# LM298.net
KiCad netlist of a schematic drawn in Altium Designer
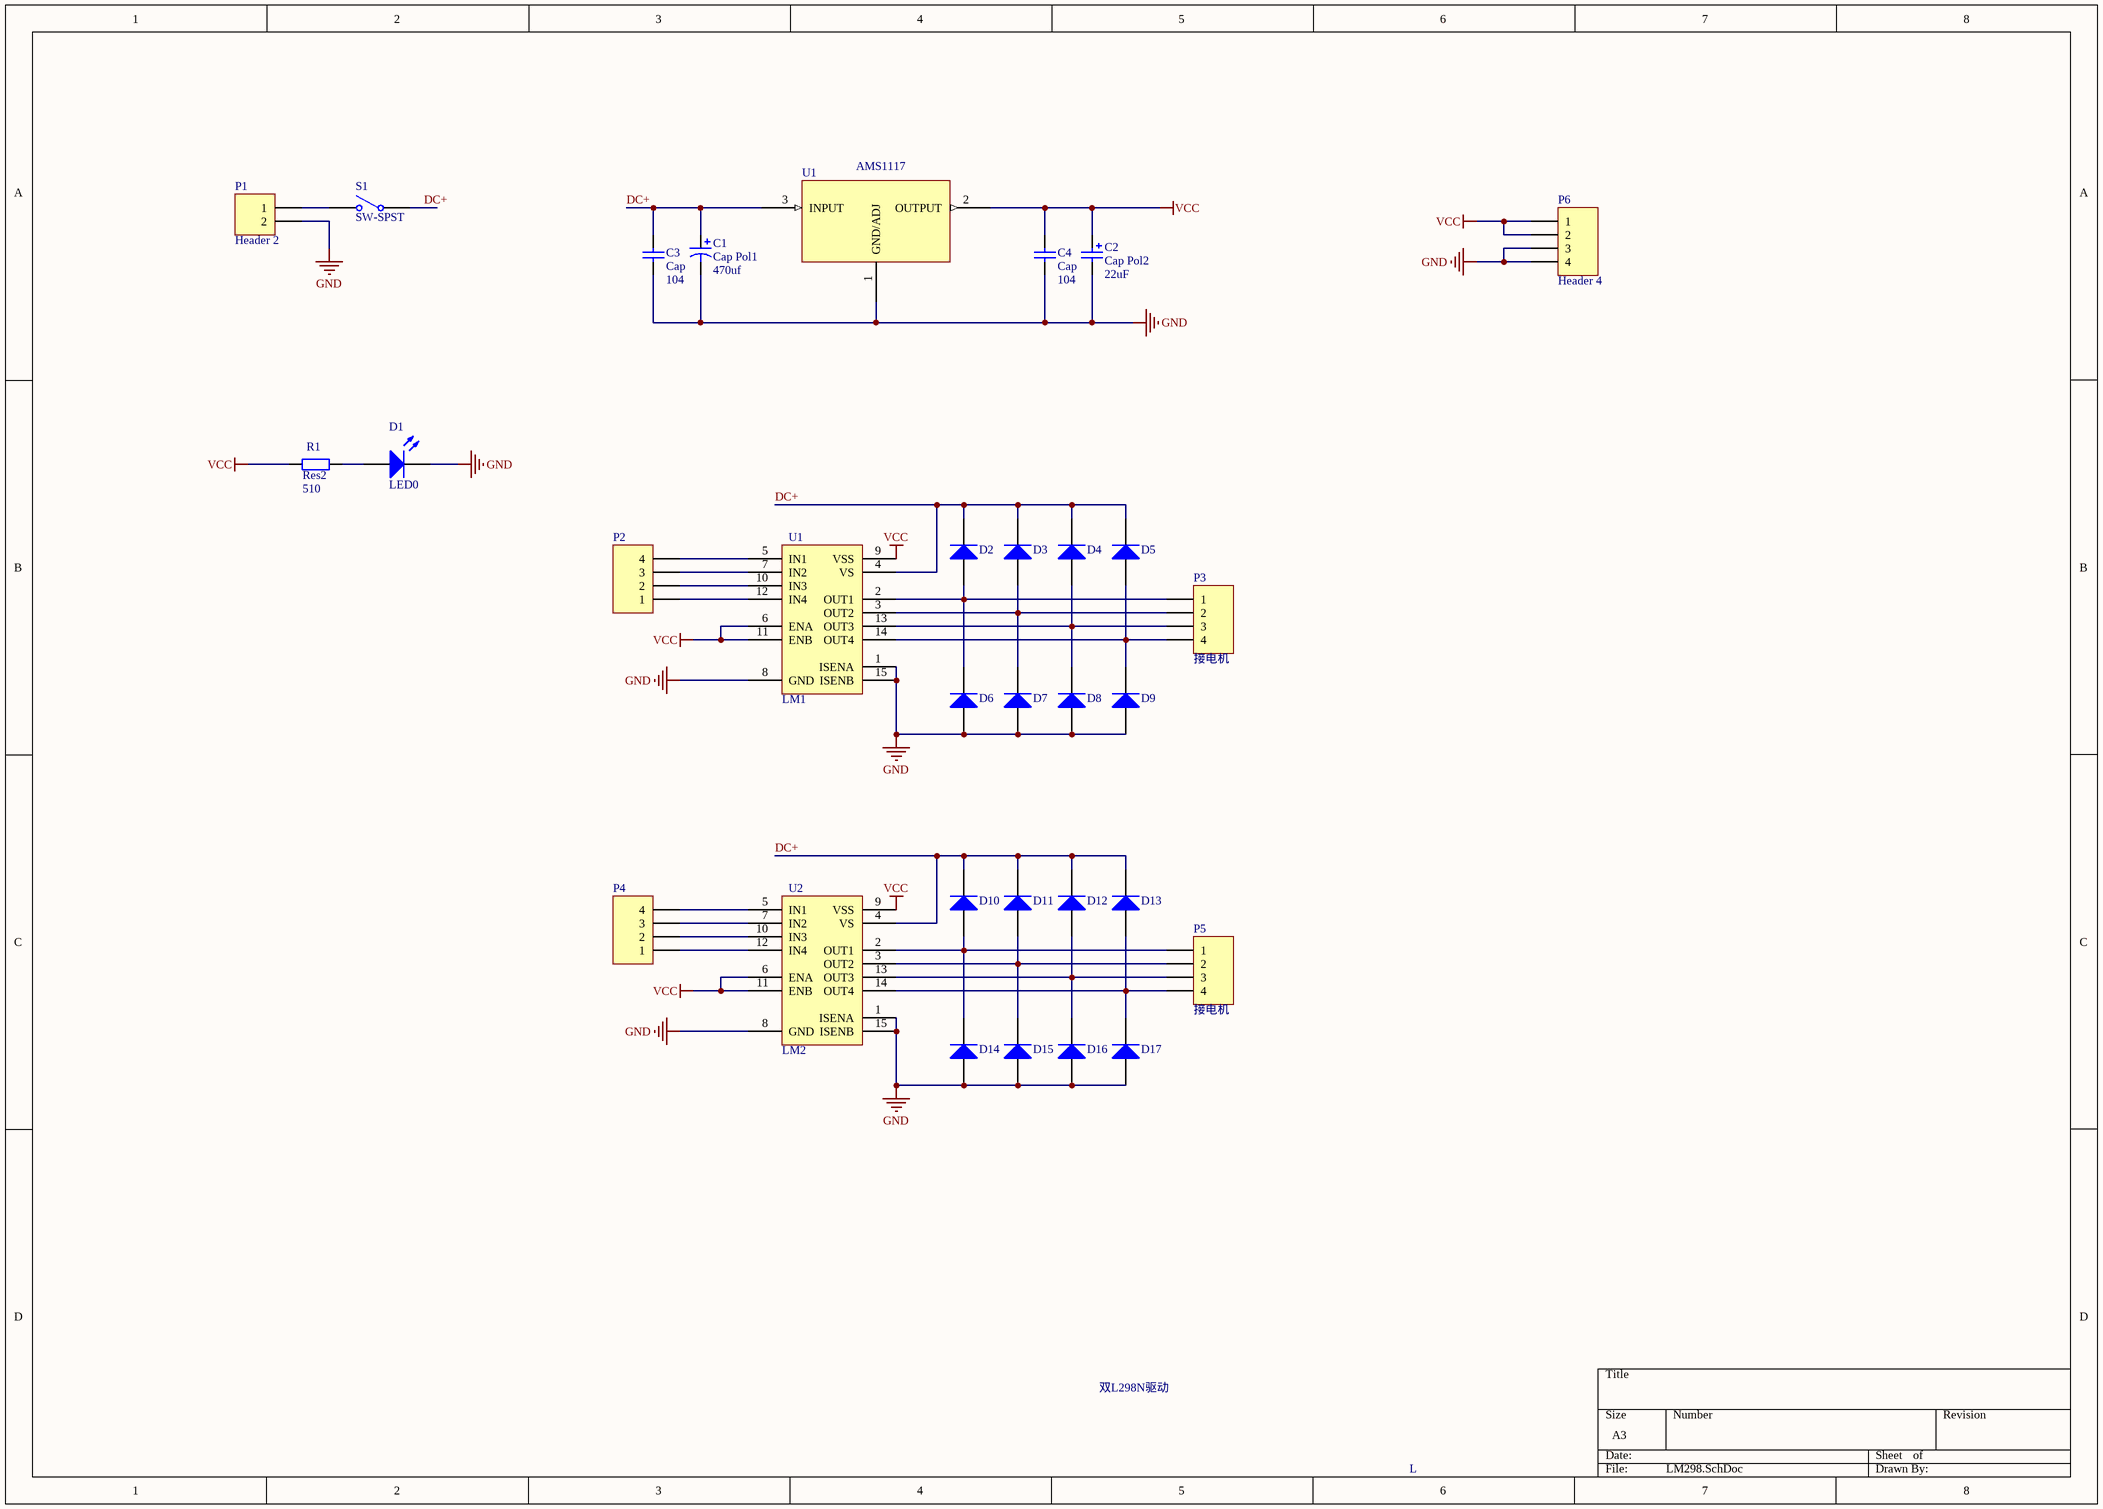
[diagram p0: LM298.SchDoc]

(export (version "E")
  (design (tool "Eeschema 10.0.6"))
  (components
    (comp (ref "C1")
      (value "Cap Pol1")
      (footprint "CAP-E1")
      (description "Polarized Capacitor (Radial)")
      (fields (field (name "ALTIUM_VALUE") "470uf") (field (name "PUBLISHER") "Altium Limited"))
      (libsource (lib "Miscellaneous Devices") (part "Cap Pol1"))
    )
    (comp (ref "C2")
      (value "Cap Pol2")
      (footprint "C-RB-8")
      (description "Polarized Capacitor (Axial)")
      (fields (field (name "ALTIUM_VALUE") "22uF") (field (name "PUBLISHER") "Altium Limited"))
      (libsource (lib "Miscellaneous Devices") (part "Cap Pol2"))
    )
    (comp (ref "C3")
      (value "Cap")
      (footprint "C-0805")
      (description "Capacitor")
      (fields (field (name "ALTIUM_VALUE") "104") (field (name "PUBLISHER") "Altium Limited"))
      (libsource (lib "Miscellaneous Devices") (part "Cap"))
    )
    (comp (ref "C4")
      (value "Cap")
      (footprint "C-0805")
      (description "Capacitor")
      (fields (field (name "ALTIUM_VALUE") "104") (field (name "PUBLISHER") "Altium Limited"))
      (libsource (lib "Miscellaneous Devices") (part "Cap"))
    )
    (comp (ref "D1")
      (value "LED0")
      (footprint "LED")
      (description "Typical INFRARED GaAs LED")
      (fields (field (name "PUBLISHER") "Altium Limited"))
      (libsource (lib "Miscellaneous Devices") (part "LED0"))
    )
    (comp (ref "D2")
      (value "Diode 1N4007")
      (footprint "DIODE-AXL")
      (description "1 Amp General Purpose Rectifier")
      (fields (field (name "PUBLISHER") "Altium Limited"))
      (libsource (lib "Miscellaneous Devices") (part "Diode 1N4007"))
    )
    (comp (ref "D3")
      (value "Diode 1N4007")
      (footprint "DIODE-AXL")
      (description "1 Amp General Purpose Rectifier")
      (fields (field (name "PUBLISHER") "Altium Limited"))
      (libsource (lib "Miscellaneous Devices") (part "Diode 1N4007"))
    )
    (comp (ref "D4")
      (value "Diode 1N4007")
      (footprint "DIODE-AXL")
      (description "1 Amp General Purpose Rectifier")
      (fields (field (name "PUBLISHER") "Altium Limited"))
      (libsource (lib "Miscellaneous Devices") (part "Diode 1N4007"))
    )
    (comp (ref "D5")
      (value "Diode 1N4007")
      (footprint "DIODE-AXL")
      (description "1 Amp General Purpose Rectifier")
      (fields (field (name "PUBLISHER") "Altium Limited"))
      (libsource (lib "Miscellaneous Devices") (part "Diode 1N4007"))
    )
    (comp (ref "D6")
      (value "Diode 1N4007")
      (footprint "DIODE-AXL")
      (description "1 Amp General Purpose Rectifier")
      (fields (field (name "PUBLISHER") "Altium Limited"))
      (libsource (lib "Miscellaneous Devices") (part "Diode 1N4007"))
    )
    (comp (ref "D7")
      (value "Diode 1N4007")
      (footprint "DIODE-AXL")
      (description "1 Amp General Purpose Rectifier")
      (fields (field (name "PUBLISHER") "Altium Limited"))
      (libsource (lib "Miscellaneous Devices") (part "Diode 1N4007"))
    )
    (comp (ref "D8")
      (value "Diode 1N4007")
      (footprint "DIODE-AXL")
      (description "1 Amp General Purpose Rectifier")
      (fields (field (name "PUBLISHER") "Altium Limited"))
      (libsource (lib "Miscellaneous Devices") (part "Diode 1N4007"))
    )
    (comp (ref "D9")
      (value "Diode 1N4007")
      (footprint "DIODE-AXL")
      (description "1 Amp General Purpose Rectifier")
      (fields (field (name "PUBLISHER") "Altium Limited"))
      (libsource (lib "Miscellaneous Devices") (part "Diode 1N4007"))
    )
    (comp (ref "D10")
      (value "Diode 1N4007")
      (footprint "DIODE-AXL")
      (description "1 Amp General Purpose Rectifier")
      (fields (field (name "PUBLISHER") "Altium Limited"))
      (libsource (lib "Miscellaneous Devices") (part "Diode 1N4007"))
    )
    (comp (ref "D11")
      (value "Diode 1N4007")
      (footprint "DIODE-AXL")
      (description "1 Amp General Purpose Rectifier")
      (fields (field (name "PUBLISHER") "Altium Limited"))
      (libsource (lib "Miscellaneous Devices") (part "Diode 1N4007"))
    )
    (comp (ref "D12")
      (value "Diode 1N4007")
      (footprint "DIODE-AXL")
      (description "1 Amp General Purpose Rectifier")
      (fields (field (name "PUBLISHER") "Altium Limited"))
      (libsource (lib "Miscellaneous Devices") (part "Diode 1N4007"))
    )
    (comp (ref "D13")
      (value "Diode 1N4007")
      (footprint "DIODE-AXL")
      (description "1 Amp General Purpose Rectifier")
      (fields (field (name "PUBLISHER") "Altium Limited"))
      (libsource (lib "Miscellaneous Devices") (part "Diode 1N4007"))
    )
    (comp (ref "D14")
      (value "Diode 1N4007")
      (footprint "DIODE-AXL")
      (description "1 Amp General Purpose Rectifier")
      (fields (field (name "PUBLISHER") "Altium Limited"))
      (libsource (lib "Miscellaneous Devices") (part "Diode 1N4007"))
    )
    (comp (ref "D15")
      (value "Diode 1N4007")
      (footprint "DIODE-AXL")
      (description "1 Amp General Purpose Rectifier")
      (fields (field (name "PUBLISHER") "Altium Limited"))
      (libsource (lib "Miscellaneous Devices") (part "Diode 1N4007"))
    )
    (comp (ref "D16")
      (value "Diode 1N4007")
      (footprint "DIODE-AXL")
      (description "1 Amp General Purpose Rectifier")
      (fields (field (name "PUBLISHER") "Altium Limited"))
      (libsource (lib "Miscellaneous Devices") (part "Diode 1N4007"))
    )
    (comp (ref "D17")
      (value "Diode 1N4007")
      (footprint "DIODE-AXL")
      (description "1 Amp General Purpose Rectifier")
      (fields (field (name "PUBLISHER") "Altium Limited"))
      (libsource (lib "Miscellaneous Devices") (part "Diode 1N4007"))
    )
    (comp (ref "LM1") (value "U1") (footprint "L298N") (libsource (lib "常用1") (part "LM298N")))
    (comp (ref "LM2") (value "U2") (footprint "L298N") (libsource (lib "常用1") (part "LM298N")))
    (comp (ref "P1")
      (value "Header 2")
      (footprint "接线柱")
      (description "Header, 2-Pin")
      (fields (field (name "PUBLISHER") "Altium Limited"))
      (libsource (lib "Miscellaneous Connectors") (part "Header 2"))
    )
    (comp (ref "P2")
      (value "~")
      (footprint "HDR1X4")
      (description "Header, 4-Pin")
      (fields (field (name "PUBLISHER") "Altium Limited"))
      (libsource (lib "") (part "Header 4_1"))
    )
    (comp (ref "P3")
      (value "接电机")
      (footprint "HDR1X4")
      (description "Header, 4-Pin")
      (fields (field (name "PUBLISHER") "Altium Limited"))
      (libsource (lib "Miscellaneous Connectors") (part "Header 4"))
    )
    (comp (ref "P4")
      (value "~")
      (footprint "HDR1X4")
      (description "Header, 4-Pin")
      (fields (field (name "PUBLISHER") "Altium Limited"))
      (libsource (lib "") (part "Header 4_1"))
    )
    (comp (ref "P5")
      (value "接电机")
      (footprint "HDR1X4")
      (description "Header, 4-Pin")
      (fields (field (name "PUBLISHER") "Altium Limited"))
      (libsource (lib "Miscellaneous Connectors") (part "Header 4"))
    )
    (comp (ref "P6")
      (value "Header 4")
      (footprint "HDR1X4")
      (description "Header, 4-Pin")
      (fields (field (name "PUBLISHER") "Altium Limited"))
      (libsource (lib "Miscellaneous Connectors") (part "Header 4"))
    )
    (comp (ref "R1")
      (value "Res2")
      (footprint "0805")
      (description "Resistor")
      (fields (field (name "ALTIUM_VALUE") "510") (field (name "PUBLISHER") "Altium Limited"))
      (libsource (lib "Miscellaneous Devices") (part "Res2"))
    )
    (comp (ref "S1")
      (value "SW-SPST")
      (footprint "SW-6pin")
      (description "Single-Pole, Single-Throw Switch")
      (fields (field (name "PUBLISHER") "Altium Limited"))
      (libsource (lib "Miscellaneous Devices") (part "SW-SPST"))
    )
    (comp (ref "U1") (value "AMS1117") (footprint "AMS1117") (libsource (lib "常用封装") (part "AMS1117")))
  )
  (nets
    (net (code "1") (name "/DC+") (class "Default")
      (node (ref "C1") (pin "1") (pinfunction "1_1") (pintype "passive"))
      (node (ref "C3") (pin "1") (pinfunction "1_1") (pintype "passive"))
      (node (ref "D10") (pin "2") (pinfunction "K_2") (pintype "passive"))
      (node (ref "D11") (pin "2") (pinfunction "K_2") (pintype "passive"))
      (node (ref "D12") (pin "2") (pinfunction "K_2") (pintype "passive"))
      (node (ref "D13") (pin "2") (pinfunction "K_2") (pintype "passive"))
      (node (ref "D2") (pin "2") (pinfunction "K_2") (pintype "passive"))
      (node (ref "D3") (pin "2") (pinfunction "K_2") (pintype "passive"))
      (node (ref "D4") (pin "2") (pinfunction "K_2") (pintype "passive"))
      (node (ref "D5") (pin "2") (pinfunction "K_2") (pintype "passive"))
      (node (ref "LM1") (pin "4") (pinfunction "VS_4") (pintype "passive"))
      (node (ref "LM2") (pin "4") (pinfunction "VS_4") (pintype "passive"))
      (node (ref "S1") (pin "1") (pinfunction "COMMON_1") (pintype "passive"))
      (node (ref "U1") (pin "3") (pinfunction "INPUT_3") (pintype "input"))
    )
    (net (code "2") (name "GND") (class "Default")
      (node (ref "C1") (pin "2") (pinfunction "2_2") (pintype "passive"))
      (node (ref "C2") (pin "2") (pinfunction "2_2") (pintype "passive"))
      (node (ref "C3") (pin "2") (pinfunction "2_2") (pintype "passive"))
      (node (ref "C4") (pin "2") (pinfunction "2_2") (pintype "passive"))
      (node (ref "D1") (pin "2") (pinfunction "K_2") (pintype "passive"))
      (node (ref "D14") (pin "1") (pinfunction "A_1") (pintype "passive"))
      (node (ref "D15") (pin "1") (pinfunction "A_1") (pintype "passive"))
      (node (ref "D16") (pin "1") (pinfunction "A_1") (pintype "passive"))
      (node (ref "D17") (pin "1") (pinfunction "A_1") (pintype "passive"))
      (node (ref "D6") (pin "1") (pinfunction "A_1") (pintype "passive"))
      (node (ref "D7") (pin "1") (pinfunction "A_1") (pintype "passive"))
      (node (ref "D8") (pin "1") (pinfunction "A_1") (pintype "passive"))
      (node (ref "D9") (pin "1") (pinfunction "A_1") (pintype "passive"))
      (node (ref "LM1") (pin "1") (pinfunction "ISENA_1") (pintype "passive"))
      (node (ref "LM1") (pin "15") (pinfunction "ISENB_15") (pintype "passive"))
      (node (ref "LM1") (pin "8") (pinfunction "GND_8") (pintype "passive"))
      (node (ref "LM2") (pin "1") (pinfunction "ISENA_1") (pintype "passive"))
      (node (ref "LM2") (pin "15") (pinfunction "ISENB_15") (pintype "passive"))
      (node (ref "LM2") (pin "8") (pinfunction "GND_8") (pintype "passive"))
      (node (ref "P1") (pin "2") (pinfunction "2_2") (pintype "passive"))
      (node (ref "P6") (pin "3") (pinfunction "3_3") (pintype "passive"))
      (node (ref "P6") (pin "4") (pinfunction "4_4") (pintype "passive"))
      (node (ref "U1") (pin "1") (pinfunction "GND/ADJ_1") (pintype "passive"))
    )
    (net (code "3") (name "Net-(D1-A)") (class "Default")
      (node (ref "D1") (pin "1") (pinfunction "A_1") (pintype "passive"))
      (node (ref "R1") (pin "2") (pinfunction "2_2") (pintype "passive"))
    )
    (net (code "4") (name "Net-(D2-A)") (class "Default")
      (node (ref "D2") (pin "1") (pinfunction "A_1") (pintype "passive"))
      (node (ref "D6") (pin "2") (pinfunction "K_2") (pintype "passive"))
      (node (ref "LM1") (pin "2") (pinfunction "OUT1_2") (pintype "passive"))
      (node (ref "P3") (pin "1") (pinfunction "1_1") (pintype "passive"))
    )
    (net (code "5") (name "Net-(D3-A)") (class "Default")
      (node (ref "D3") (pin "1") (pinfunction "A_1") (pintype "passive"))
      (node (ref "D7") (pin "2") (pinfunction "K_2") (pintype "passive"))
      (node (ref "LM1") (pin "3") (pinfunction "OUT2_3") (pintype "passive"))
      (node (ref "P3") (pin "2") (pinfunction "2_2") (pintype "passive"))
    )
    (net (code "6") (name "Net-(D4-A)") (class "Default")
      (node (ref "D4") (pin "1") (pinfunction "A_1") (pintype "passive"))
      (node (ref "D8") (pin "2") (pinfunction "K_2") (pintype "passive"))
      (node (ref "LM1") (pin "13") (pinfunction "OUT3_13") (pintype "passive"))
      (node (ref "P3") (pin "3") (pinfunction "3_3") (pintype "passive"))
    )
    (net (code "7") (name "Net-(D5-A)") (class "Default")
      (node (ref "D5") (pin "1") (pinfunction "A_1") (pintype "passive"))
      (node (ref "D9") (pin "2") (pinfunction "K_2") (pintype "passive"))
      (node (ref "LM1") (pin "14") (pinfunction "OUT4_14") (pintype "passive"))
      (node (ref "P3") (pin "4") (pinfunction "4_4") (pintype "passive"))
    )
    (net (code "8") (name "Net-(D10-A)") (class "Default")
      (node (ref "D10") (pin "1") (pinfunction "A_1") (pintype "passive"))
      (node (ref "D14") (pin "2") (pinfunction "K_2") (pintype "passive"))
      (node (ref "LM2") (pin "2") (pinfunction "OUT1_2") (pintype "passive"))
      (node (ref "P5") (pin "1") (pinfunction "1_1") (pintype "passive"))
    )
    (net (code "9") (name "Net-(D11-A)") (class "Default")
      (node (ref "D11") (pin "1") (pinfunction "A_1") (pintype "passive"))
      (node (ref "D15") (pin "2") (pinfunction "K_2") (pintype "passive"))
      (node (ref "LM2") (pin "3") (pinfunction "OUT2_3") (pintype "passive"))
      (node (ref "P5") (pin "2") (pinfunction "2_2") (pintype "passive"))
    )
    (net (code "10") (name "Net-(D12-A)") (class "Default")
      (node (ref "D12") (pin "1") (pinfunction "A_1") (pintype "passive"))
      (node (ref "D16") (pin "2") (pinfunction "K_2") (pintype "passive"))
      (node (ref "LM2") (pin "13") (pinfunction "OUT3_13") (pintype "passive"))
      (node (ref "P5") (pin "3") (pinfunction "3_3") (pintype "passive"))
    )
    (net (code "11") (name "Net-(D13-A)") (class "Default")
      (node (ref "D13") (pin "1") (pinfunction "A_1") (pintype "passive"))
      (node (ref "D17") (pin "2") (pinfunction "K_2") (pintype "passive"))
      (node (ref "LM2") (pin "14") (pinfunction "OUT4_14") (pintype "passive"))
      (node (ref "P5") (pin "4") (pinfunction "4_4") (pintype "passive"))
    )
    (net (code "12") (name "Net-(LM1-IN1)") (class "Default")
      (node (ref "LM1") (pin "5") (pinfunction "IN1_5") (pintype "passive"))
      (node (ref "P2") (pin "4") (pinfunction "4_4") (pintype "passive"))
    )
    (net (code "13") (name "Net-(LM1-IN2)") (class "Default")
      (node (ref "LM1") (pin "7") (pinfunction "IN2_7") (pintype "passive"))
      (node (ref "P2") (pin "3") (pinfunction "3_3") (pintype "passive"))
    )
    (net (code "14") (name "Net-(LM1-IN3)") (class "Default")
      (node (ref "LM1") (pin "10") (pinfunction "IN3_10") (pintype "passive"))
      (node (ref "P2") (pin "2") (pinfunction "2_2") (pintype "passive"))
    )
    (net (code "15") (name "Net-(LM1-IN4)") (class "Default")
      (node (ref "LM1") (pin "12") (pinfunction "IN4_12") (pintype "passive"))
      (node (ref "P2") (pin "1") (pinfunction "1_1") (pintype "passive"))
    )
    (net (code "16") (name "Net-(LM2-IN1)") (class "Default")
      (node (ref "LM2") (pin "5") (pinfunction "IN1_5") (pintype "passive"))
      (node (ref "P4") (pin "4") (pinfunction "4_4") (pintype "passive"))
    )
    (net (code "17") (name "Net-(LM2-IN2)") (class "Default")
      (node (ref "LM2") (pin "7") (pinfunction "IN2_7") (pintype "passive"))
      (node (ref "P4") (pin "3") (pinfunction "3_3") (pintype "passive"))
    )
    (net (code "18") (name "Net-(LM2-IN3)") (class "Default")
      (node (ref "LM2") (pin "10") (pinfunction "IN3_10") (pintype "passive"))
      (node (ref "P4") (pin "2") (pinfunction "2_2") (pintype "passive"))
    )
    (net (code "19") (name "Net-(LM2-IN4)") (class "Default")
      (node (ref "LM2") (pin "12") (pinfunction "IN4_12") (pintype "passive"))
      (node (ref "P4") (pin "1") (pinfunction "1_1") (pintype "passive"))
    )
    (net (code "20") (name "Net-(S1-NO)") (class "Default")
      (node (ref "P1") (pin "1") (pinfunction "1_1") (pintype "passive"))
      (node (ref "S1") (pin "2") (pinfunction "NO_2") (pintype "passive"))
    )
    (net (code "21") (name "VCC") (class "Default")
      (node (ref "C2") (pin "1") (pinfunction "1_1") (pintype "passive"))
      (node (ref "C4") (pin "1") (pinfunction "1_1") (pintype "passive"))
      (node (ref "LM1") (pin "11") (pinfunction "ENB_11") (pintype "passive"))
      (node (ref "LM1") (pin "6") (pinfunction "ENA_6") (pintype "passive"))
      (node (ref "LM1") (pin "9") (pinfunction "VSS_9") (pintype "passive"))
      (node (ref "LM2") (pin "11") (pinfunction "ENB_11") (pintype "passive"))
      (node (ref "LM2") (pin "6") (pinfunction "ENA_6") (pintype "passive"))
      (node (ref "LM2") (pin "9") (pinfunction "VSS_9") (pintype "passive"))
      (node (ref "P6") (pin "1") (pinfunction "1_1") (pintype "passive"))
      (node (ref "P6") (pin "2") (pinfunction "2_2") (pintype "passive"))
      (node (ref "R1") (pin "1") (pinfunction "1_1") (pintype "passive"))
      (node (ref "U1") (pin "2") (pinfunction "OUTPUT_2") (pintype "output"))
    )
  )
)
